# AT89S52.net
KiCad netlist of a schematic drawn in Altium Designer
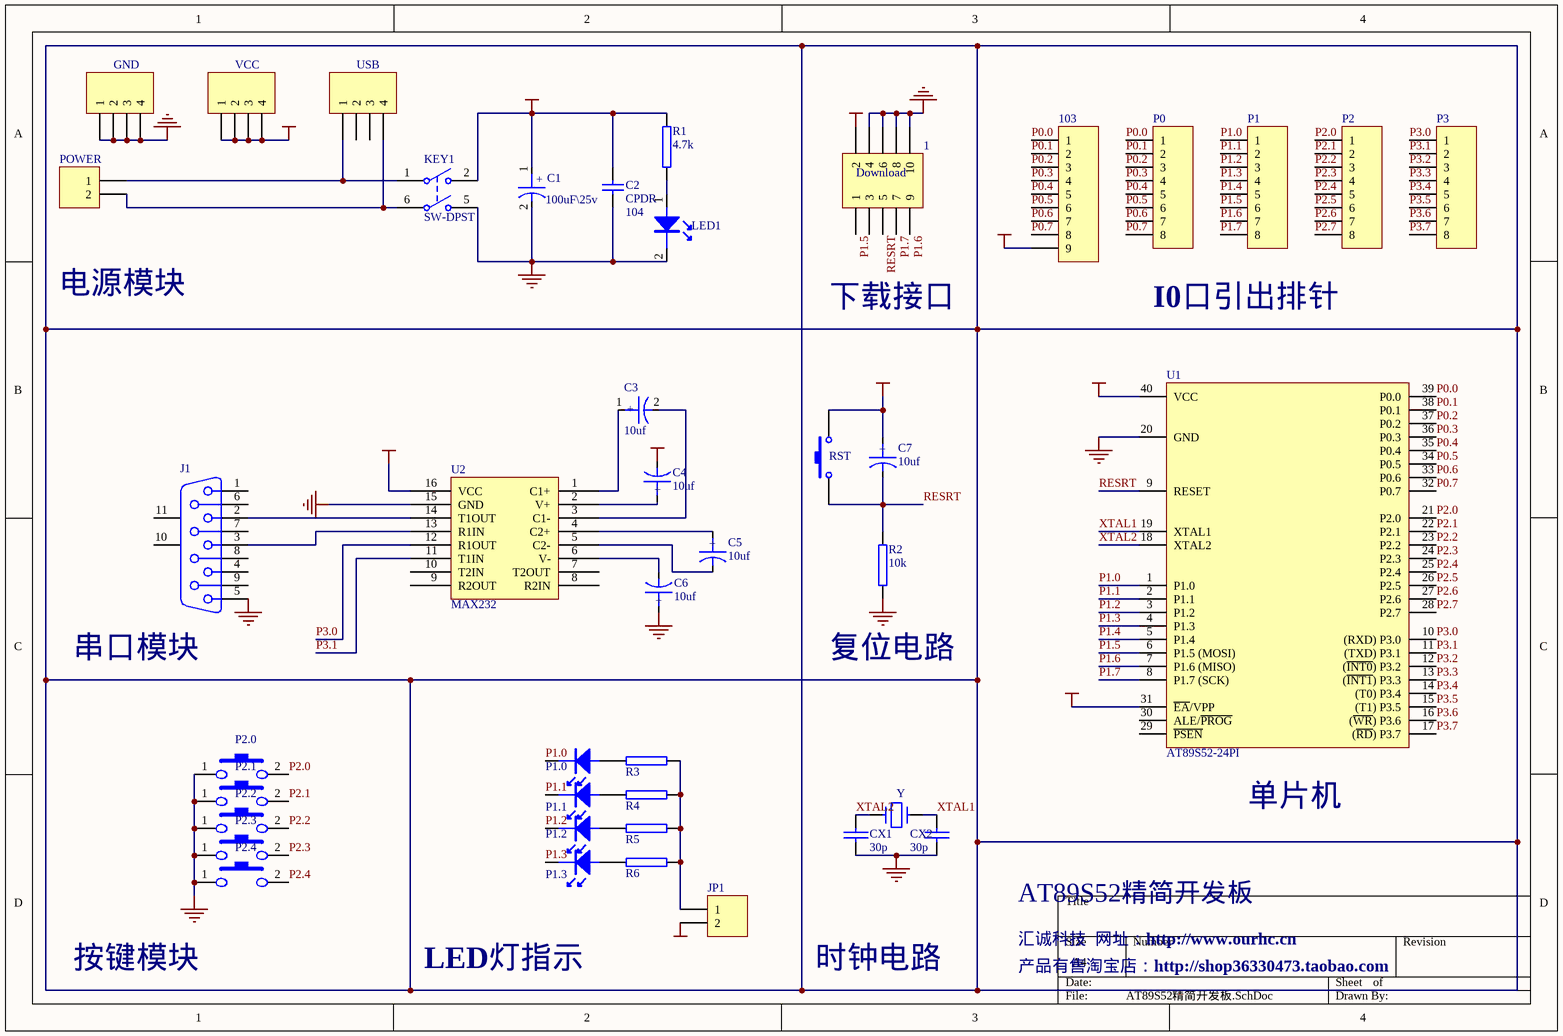
[diagram p0: AT89S52精简开发板.SchDoc]

(export (version "E")
  (design (tool "Eeschema 10.0.6"))
  (components
    (comp (ref "1")
      (value "Download")
      (footprint "HDR-2x5")
      (description "Header, 5-Pin, Dual row")
      (fields (field (name "PUBLISHER") "Altium Limited"))
      (libsource (lib "Miscellaneous Connectors") (part "Header 5X2"))
    )
    (comp (ref "103")
      (value "~")
      (footprint "HDR-9")
      (description "排针——9")
      (fields (field (name "PUBLISHER") "Altium Limited"))
      (libsource (lib "zxcourhc") (part "PZ_9"))
    )
    (comp (ref "C1")
      (value "100u~{F}25v")
      (footprint "C-DJ-6")
      (description "Capacitor")
      (libsource (lib "OldCow1 (1)") (part "CAPACITOR POL"))
    )
    (comp (ref "C2")
      (value "CPDR")
      (footprint "CPDR")
      (description "瓷片电容")
      (fields (field (name "ALTIUM_VALUE") "104") (field (name "PUBLISHER") "Altium Limited"))
      (libsource (lib "zxcourhc") (part "CPDR"))
    )
    (comp (ref "C3")
      (value "10uf")
      (footprint "C-DJ-4")
      (description "Capacitor")
      (libsource (lib "") (part "CAPACITOR POL_1"))
    )
    (comp (ref "C4")
      (value "10uf")
      (footprint "C-DJ-4")
      (description "Capacitor")
      (libsource (lib "*") (part "CAPACITOR POL"))
    )
    (comp (ref "C5")
      (value "10uf")
      (footprint "C-DJ-4")
      (description "Capacitor")
      (libsource (lib "*") (part "CAPACITOR POL"))
    )
    (comp (ref "C6")
      (value "10uf")
      (footprint "C-DJ-4")
      (description "Capacitor")
      (libsource (lib "*") (part "CAPACITOR POL"))
    )
    (comp (ref "C7")
      (value "10uf")
      (footprint "C-DJ-4")
      (description "Capacitor")
      (libsource (lib "*") (part "CAPACITOR POL"))
    )
    (comp (ref "CX1")
      (value "30p")
      (footprint "HDR1X2")
      (description "Capacitor")
      (libsource (lib "*") (part "CAP"))
    )
    (comp (ref "CX2")
      (value "30p")
      (footprint "HDR1X2")
      (description "Capacitor")
      (libsource (lib "*") (part "CAP"))
    )
    (comp (ref "GND")
      (value "~")
      (footprint "HDR1X4")
      (description "Header, 4-Pin")
      (fields (field (name "PUBLISHER") "Altium Limited"))
      (libsource (lib "Miscellaneous Connectors") (part "Header 4"))
    )
    (comp (ref "J1")
      (value "D Connector 9")
      (footprint "DSUB1.385-2H9")
      (description "Receptacle Assembly, 9 Position, Right Angle")
      (fields (field (name "PUBLISHER") "Altium Limited"))
      (libsource (lib "Miscellaneous Connectors") (part "D Connector 9"))
    )
    (comp (ref "JP1")
      (value "~")
      (footprint "HDR1X2")
      (description "Header, 2-Pin")
      (fields (field (name "PUBLISHER") "Altium Limited"))
      (libsource (lib "") (part "Header 2_1"))
    )
    (comp (ref "KEY1")
      (value "SW-DPST")
      (footprint "DPDT-6")
      (description "Double-Pole, Single-Throw Switch")
      (fields (field (name "PUBLISHER") "Altium Limited"))
      (libsource (lib "Miscellaneous Devices") (part "SW-DPST"))
    )
    (comp (ref "LED1") (value "LED") (footprint "LED") (libsource (lib "") (part "LED_1")))
    (comp (ref "P0")
      (value "~")
      (footprint "HDR-8")
      (description "排针——8")
      (fields (field (name "PUBLISHER") "Altium Limited"))
      (libsource (lib "zxcourhc") (part "PZ_8"))
    )
    (comp (ref "P1")
      (value "~")
      (footprint "HDR-8")
      (description "排针——8")
      (fields (field (name "PUBLISHER") "Altium Limited"))
      (libsource (lib "zxcourhc") (part "PZ_8"))
    )
    (comp (ref "P1.0") (value "LED") (footprint "HDR1X2") (libsource (lib "OldCow1 (1)") (part "LED")))
    (comp (ref "P1.1") (value "LED") (footprint "HDR1X2") (libsource (lib "OldCow1 (1)") (part "LED")))
    (comp (ref "P1.2") (value "LED") (footprint "HDR1X2") (libsource (lib "OldCow1 (1)") (part "LED")))
    (comp (ref "P1.3") (value "LED") (footprint "HDR1X2") (libsource (lib "OldCow1 (1)") (part "LED")))
    (comp (ref "P2")
      (value "~")
      (footprint "HDR-8")
      (description "排针——8")
      (fields (field (name "PUBLISHER") "Altium Limited"))
      (libsource (lib "zxcourhc") (part "PZ_8"))
    )
    (comp (ref "P2.0") (value "key1") (footprint "an-6*6") (libsource (lib "OldCow1 (1)") (part "key")))
    (comp (ref "P2.1") (value "key2") (footprint "an-6*6") (libsource (lib "OldCow1 (1)") (part "key")))
    (comp (ref "P2.2") (value "key3") (footprint "an-6*6") (libsource (lib "OldCow1 (1)") (part "key")))
    (comp (ref "P2.3") (value "key4") (footprint "an-6*6") (libsource (lib "OldCow1 (1)") (part "key")))
    (comp (ref "P2.4") (value "key4") (footprint "an-6*6") (libsource (lib "OldCow1 (1)") (part "key")))
    (comp (ref "P3")
      (value "~")
      (footprint "HDR-8")
      (description "排针——8")
      (fields (field (name "PUBLISHER") "Altium Limited"))
      (libsource (lib "zxcourhc") (part "PZ_8"))
    )
    (comp (ref "POWER")
      (value "~")
      (footprint "JK128")
      (description "Header, 2-Pin")
      (fields (field (name "PUBLISHER") "Altium Limited"))
      (libsource (lib "Miscellaneous Connectors") (part "Header 2"))
    )
    (comp (ref "R1") (value "4.7k") (footprint "RSE") (libsource (lib "*") (part "RES2")))
    (comp (ref "R2") (value "10k") (footprint "RSE") (libsource (lib "*") (part "RES2")))
    (comp (ref "R3") (value "470") (footprint "RSE") (libsource (lib "*") (part "RES2")))
    (comp (ref "R4") (value "470") (footprint "RSE") (libsource (lib "*") (part "RES2")))
    (comp (ref "R5") (value "470") (footprint "RSE") (libsource (lib "*") (part "RES2")))
    (comp (ref "R6") (value "470") (footprint "RSE") (libsource (lib "*") (part "RES2")))
    (comp (ref "RST")
      (value "~")
      (footprint "an-6*6")
      (description "Switch")
      (fields (field (name "PUBLISHER") "Altium Limited"))
      (libsource (lib "Miscellaneous Devices") (part "SW-PB"))
    )
    (comp (ref "U1")
      (value "AT89S52-24PI")
      (footprint "DIP-40")
      (description "8 位微处理器/40引脚")
      (fields (field (name "发布者") "磊元工作室"))
      (libsource (lib "MCU") (part "AT89S52-P"))
    )
    (comp (ref "U2") (value "MAX232") (footprint "DIP16") (libsource (lib "*") (part "MAX232")))
    (comp (ref "USB")
      (value "~")
      (footprint "USB-5V")
      (description "Header, 4-Pin")
      (fields (field (name "PUBLISHER") "Altium Limited"))
      (libsource (lib "Miscellaneous Connectors") (part "Header 4"))
    )
    (comp (ref "VCC")
      (value "~")
      (footprint "HDR1X4")
      (description "Header, 4-Pin")
      (fields (field (name "PUBLISHER") "Altium Limited"))
      (libsource (lib "Miscellaneous Connectors") (part "Header 4"))
    )
    (comp (ref "Y1")
      (value "Y")
      (footprint "JZ_ZC")
      (description "Crystal")
      (libsource (lib "*") (part "CRYSTAL"))
    )
  )
  (nets
    (net (code "1") (name "/P0.0") (class "Default")
      (node (ref "103") (pin "1") (pinfunction "1_1") (pintype "passive"))
      (node (ref "P0") (pin "1") (pinfunction "1_1") (pintype "passive"))
      (node (ref "U1") (pin "39") (pinfunction "P0.0_39") (pintype "passive"))
    )
    (net (code "2") (name "/P0.1") (class "Default")
      (node (ref "103") (pin "2") (pinfunction "2_2") (pintype "passive"))
      (node (ref "P0") (pin "2") (pinfunction "2_2") (pintype "passive"))
      (node (ref "U1") (pin "38") (pinfunction "P0.1_38") (pintype "passive"))
    )
    (net (code "3") (name "/P0.2") (class "Default")
      (node (ref "103") (pin "3") (pinfunction "3_3") (pintype "passive"))
      (node (ref "P0") (pin "3") (pinfunction "3_3") (pintype "passive"))
      (node (ref "U1") (pin "37") (pinfunction "P0.2_37") (pintype "passive"))
    )
    (net (code "4") (name "/P0.3") (class "Default")
      (node (ref "103") (pin "4") (pinfunction "4_4") (pintype "passive"))
      (node (ref "P0") (pin "4") (pinfunction "4_4") (pintype "passive"))
      (node (ref "U1") (pin "36") (pinfunction "P0.3_36") (pintype "passive"))
    )
    (net (code "5") (name "/P0.4") (class "Default")
      (node (ref "103") (pin "5") (pinfunction "5_5") (pintype "passive"))
      (node (ref "P0") (pin "5") (pinfunction "5_5") (pintype "passive"))
      (node (ref "U1") (pin "35") (pinfunction "P0.4_35") (pintype "passive"))
    )
    (net (code "6") (name "/P0.5") (class "Default")
      (node (ref "103") (pin "6") (pinfunction "6_6") (pintype "passive"))
      (node (ref "P0") (pin "6") (pinfunction "6_6") (pintype "passive"))
      (node (ref "U1") (pin "34") (pinfunction "P0.5_34") (pintype "passive"))
    )
    (net (code "7") (name "/P0.6") (class "Default")
      (node (ref "103") (pin "7") (pinfunction "7_7") (pintype "passive"))
      (node (ref "P0") (pin "7") (pinfunction "7_7") (pintype "passive"))
      (node (ref "U1") (pin "33") (pinfunction "P0.6_33") (pintype "passive"))
    )
    (net (code "8") (name "/P0.7") (class "Default")
      (node (ref "103") (pin "8") (pinfunction "8_8") (pintype "passive"))
      (node (ref "P0") (pin "8") (pinfunction "8_8") (pintype "passive"))
      (node (ref "U1") (pin "32") (pinfunction "P0.7_32") (pintype "passive"))
    )
    (net (code "9") (name "/P1.0") (class "Default")
      (node (ref "P1") (pin "1") (pinfunction "1_1") (pintype "passive"))
      (node (ref "P1.0") (pin "2") (pinfunction "K_2") (pintype "passive"))
      (node (ref "U1") (pin "1") (pinfunction "P1.0_1") (pintype "passive"))
    )
    (net (code "10") (name "/P1.1") (class "Default")
      (node (ref "P1") (pin "2") (pinfunction "2_2") (pintype "passive"))
      (node (ref "P1.1") (pin "2") (pinfunction "K_2") (pintype "passive"))
      (node (ref "U1") (pin "2") (pinfunction "P1.1_2") (pintype "passive"))
    )
    (net (code "11") (name "/P1.2") (class "Default")
      (node (ref "P1") (pin "3") (pinfunction "3_3") (pintype "passive"))
      (node (ref "P1.2") (pin "2") (pinfunction "K_2") (pintype "passive"))
      (node (ref "U1") (pin "3") (pinfunction "P1.2_3") (pintype "passive"))
    )
    (net (code "12") (name "/P1.3") (class "Default")
      (node (ref "P1") (pin "4") (pinfunction "4_4") (pintype "passive"))
      (node (ref "P1.3") (pin "2") (pinfunction "K_2") (pintype "passive"))
      (node (ref "U1") (pin "4") (pinfunction "P1.3_4") (pintype "passive"))
    )
    (net (code "13") (name "/P1.4") (class "Default")
      (node (ref "P1") (pin "5") (pinfunction "5_5") (pintype "passive"))
      (node (ref "U1") (pin "5") (pinfunction "P1.4_5") (pintype "passive"))
    )
    (net (code "14") (name "/P1.5") (class "Default")
      (node (ref "1") (pin "1") (pinfunction "1_1") (pintype "passive"))
      (node (ref "P1") (pin "6") (pinfunction "6_6") (pintype "passive"))
      (node (ref "U1") (pin "6") (pinfunction "P1.5_(MOSI)_6") (pintype "passive"))
    )
    (net (code "15") (name "/P1.6") (class "Default")
      (node (ref "1") (pin "9") (pinfunction "9_9") (pintype "passive"))
      (node (ref "P1") (pin "7") (pinfunction "7_7") (pintype "passive"))
      (node (ref "U1") (pin "7") (pinfunction "P1.6_(MISO)_7") (pintype "passive"))
    )
    (net (code "16") (name "/P1.7") (class "Default")
      (node (ref "1") (pin "7") (pinfunction "7_7") (pintype "passive"))
      (node (ref "P1") (pin "8") (pinfunction "8_8") (pintype "passive"))
      (node (ref "U1") (pin "8") (pinfunction "P1.7_(SCK)_8") (pintype "passive"))
    )
    (net (code "17") (name "/P2.0") (class "Default")
      (node (ref "P2") (pin "1") (pinfunction "1_1") (pintype "passive"))
      (node (ref "P2.0") (pin "2") (pinfunction "2_2") (pintype "passive"))
      (node (ref "U1") (pin "21") (pinfunction "P2.0_21") (pintype "passive"))
    )
    (net (code "18") (name "/P2.1") (class "Default")
      (node (ref "P2") (pin "2") (pinfunction "2_2") (pintype "passive"))
      (node (ref "P2.1") (pin "2") (pinfunction "2_2") (pintype "passive"))
      (node (ref "U1") (pin "22") (pinfunction "P2.1_22") (pintype "passive"))
    )
    (net (code "19") (name "/P2.2") (class "Default")
      (node (ref "P2") (pin "3") (pinfunction "3_3") (pintype "passive"))
      (node (ref "P2.2") (pin "2") (pinfunction "2_2") (pintype "passive"))
      (node (ref "U1") (pin "23") (pinfunction "P2.2_23") (pintype "passive"))
    )
    (net (code "20") (name "/P2.3") (class "Default")
      (node (ref "P2") (pin "4") (pinfunction "4_4") (pintype "passive"))
      (node (ref "P2.3") (pin "2") (pinfunction "2_2") (pintype "passive"))
      (node (ref "U1") (pin "24") (pinfunction "P2.3_24") (pintype "passive"))
    )
    (net (code "21") (name "/P2.4") (class "Default")
      (node (ref "P2") (pin "5") (pinfunction "5_5") (pintype "passive"))
      (node (ref "P2.4") (pin "2") (pinfunction "2_2") (pintype "passive"))
      (node (ref "U1") (pin "25") (pinfunction "P2.4_25") (pintype "passive"))
    )
    (net (code "22") (name "/P2.5") (class "Default")
      (node (ref "P2") (pin "6") (pinfunction "6_6") (pintype "passive"))
      (node (ref "U1") (pin "26") (pinfunction "P2.5_26") (pintype "passive"))
    )
    (net (code "23") (name "/P2.6") (class "Default")
      (node (ref "P2") (pin "7") (pinfunction "7_7") (pintype "passive"))
      (node (ref "U1") (pin "27") (pinfunction "P2.6_27") (pintype "passive"))
    )
    (net (code "24") (name "/P2.7") (class "Default")
      (node (ref "P2") (pin "8") (pinfunction "8_8") (pintype "passive"))
      (node (ref "U1") (pin "28") (pinfunction "P2.7_28") (pintype "passive"))
    )
    (net (code "25") (name "/P3.0") (class "Default")
      (node (ref "P3") (pin "1") (pinfunction "1_1") (pintype "passive"))
      (node (ref "U1") (pin "10") (pinfunction "(RXD)_P3.0_10") (pintype "passive"))
      (node (ref "U2") (pin "12") (pinfunction "R1OUT_12") (pintype "passive"))
    )
    (net (code "26") (name "/P3.1") (class "Default")
      (node (ref "P3") (pin "2") (pinfunction "2_2") (pintype "passive"))
      (node (ref "U1") (pin "11") (pinfunction "(TXD)_P3.1_11") (pintype "passive"))
      (node (ref "U2") (pin "11") (pinfunction "T1IN_11") (pintype "passive"))
    )
    (net (code "27") (name "/P3.2") (class "Default")
      (node (ref "P3") (pin "3") (pinfunction "3_3") (pintype "passive"))
      (node (ref "U1") (pin "12") (pinfunction "(~{INT0})_P3.2_12") (pintype "passive"))
    )
    (net (code "28") (name "/P3.3") (class "Default")
      (node (ref "P3") (pin "4") (pinfunction "4_4") (pintype "passive"))
      (node (ref "U1") (pin "13") (pinfunction "(~{INT1})_P3.3_13") (pintype "passive"))
    )
    (net (code "29") (name "/P3.4") (class "Default")
      (node (ref "P3") (pin "5") (pinfunction "5_5") (pintype "passive"))
      (node (ref "U1") (pin "14") (pinfunction "(T0)_P3.4_14") (pintype "passive"))
    )
    (net (code "30") (name "/P3.5") (class "Default")
      (node (ref "P3") (pin "6") (pinfunction "6_6") (pintype "passive"))
      (node (ref "U1") (pin "15") (pinfunction "(T1)_P3.5_15") (pintype "passive"))
    )
    (net (code "31") (name "/P3.6") (class "Default")
      (node (ref "P3") (pin "7") (pinfunction "7_7") (pintype "passive"))
      (node (ref "U1") (pin "16") (pinfunction "(~{WR})_P3.6_16") (pintype "passive"))
    )
    (net (code "32") (name "/P3.7") (class "Default")
      (node (ref "P3") (pin "8") (pinfunction "8_8") (pintype "passive"))
      (node (ref "U1") (pin "17") (pinfunction "(~{RD})_P3.7_17") (pintype "passive"))
    )
    (net (code "33") (name "/RESRT") (class "Default")
      (node (ref "1") (pin "5") (pinfunction "5_5") (pintype "passive"))
      (node (ref "C7") (pin "2") (pinfunction "2_2") (pintype "passive"))
      (node (ref "R2") (pin "2") (pinfunction "2_2") (pintype "passive"))
      (node (ref "RST") (pin "2") (pinfunction "2_2") (pintype "passive"))
      (node (ref "U1") (pin "9") (pinfunction "RESET_9") (pintype "passive"))
    )
    (net (code "34") (name "/XTAL1") (class "Default")
      (node (ref "CX2") (pin "1") (pinfunction "1_1") (pintype "passive"))
      (node (ref "U1") (pin "19") (pinfunction "XTAL1_19") (pintype "passive"))
      (node (ref "Y1") (pin "1") (pinfunction "1_1") (pintype "passive"))
    )
    (net (code "35") (name "/XTAL2") (class "Default")
      (node (ref "CX1") (pin "1") (pinfunction "1_1") (pintype "passive"))
      (node (ref "U1") (pin "18") (pinfunction "XTAL2_18") (pintype "passive"))
      (node (ref "Y1") (pin "2") (pinfunction "2_2") (pintype "passive"))
    )
    (net (code "36") (name "GND") (class "Default")
      (node (ref "1") (pin "10") (pinfunction "10_10") (pintype "passive"))
      (node (ref "1") (pin "4") (pinfunction "4_4") (pintype "passive"))
      (node (ref "1") (pin "6") (pinfunction "6_6") (pintype "passive"))
      (node (ref "1") (pin "8") (pinfunction "8_8") (pintype "passive"))
      (node (ref "C1") (pin "2") (pinfunction "2_2") (pintype "passive"))
      (node (ref "C2") (pin "1") (pinfunction "1_1") (pintype "passive"))
      (node (ref "C6") (pin "1") (pinfunction "1_1") (pintype "passive"))
      (node (ref "CX1") (pin "2") (pinfunction "2_2") (pintype "passive"))
      (node (ref "CX2") (pin "2") (pinfunction "2_2") (pintype "passive"))
      (node (ref "GND") (pin "1") (pinfunction "1_1") (pintype "passive"))
      (node (ref "GND") (pin "2") (pinfunction "2_2") (pintype "passive"))
      (node (ref "GND") (pin "3") (pinfunction "3_3") (pintype "passive"))
      (node (ref "GND") (pin "4") (pinfunction "4_4") (pintype "passive"))
      (node (ref "J1") (pin "5") (pinfunction "5_5") (pintype "passive"))
      (node (ref "KEY1") (pin "5") (pinfunction "NO2_5") (pintype "passive"))
      (node (ref "LED1") (pin "2") (pinfunction "K_2") (pintype "passive"))
      (node (ref "P2.0") (pin "1") (pinfunction "1_1") (pintype "passive"))
      (node (ref "P2.1") (pin "1") (pinfunction "1_1") (pintype "passive"))
      (node (ref "P2.2") (pin "1") (pinfunction "1_1") (pintype "passive"))
      (node (ref "P2.3") (pin "1") (pinfunction "1_1") (pintype "passive"))
      (node (ref "P2.4") (pin "1") (pinfunction "1_1") (pintype "passive"))
      (node (ref "R2") (pin "1") (pinfunction "1_1") (pintype "passive"))
      (node (ref "U1") (pin "20") (pinfunction "GND_20") (pintype "power_in"))
      (node (ref "U2") (pin "15") (pinfunction "GND_15") (pintype "passive"))
    )
    (net (code "37") (name "Net-(JP1-Pad1)") (class "Default")
      (node (ref "JP1") (pin "1") (pinfunction "1_1") (pintype "passive"))
      (node (ref "R3") (pin "1") (pinfunction "1_1") (pintype "passive"))
      (node (ref "R4") (pin "1") (pinfunction "1_1") (pintype "passive"))
      (node (ref "R5") (pin "1") (pinfunction "1_1") (pintype "passive"))
      (node (ref "R6") (pin "1") (pinfunction "1_1") (pintype "passive"))
    )
    (net (code "38") (name "Net-(KEY1-COMMON1)") (class "Default")
      (node (ref "KEY1") (pin "1") (pinfunction "COMMON1_1") (pintype "passive"))
      (node (ref "POWER") (pin "1") (pinfunction "1_1") (pintype "passive"))
      (node (ref "USB") (pin "1") (pinfunction "1_1") (pintype "passive"))
    )
    (net (code "39") (name "Net-(KEY1-COMMON2)") (class "Default")
      (node (ref "KEY1") (pin "6") (pinfunction "COMMON2_6") (pintype "passive"))
      (node (ref "POWER") (pin "2") (pinfunction "2_2") (pintype "passive"))
      (node (ref "USB") (pin "4") (pinfunction "4_4") (pintype "passive"))
    )
    (net (code "40") (name "Net-(LED1-A)") (class "Default")
      (node (ref "LED1") (pin "1") (pinfunction "A_1") (pintype "passive"))
      (node (ref "R1") (pin "2") (pinfunction "2_2") (pintype "passive"))
    )
    (net (code "41") (name "Net-(P1.0-A)") (class "Default")
      (node (ref "P1.0") (pin "1") (pinfunction "A_1") (pintype "passive"))
      (node (ref "R3") (pin "2") (pinfunction "2_2") (pintype "passive"))
    )
    (net (code "42") (name "Net-(P1.1-A)") (class "Default")
      (node (ref "P1.1") (pin "1") (pinfunction "A_1") (pintype "passive"))
      (node (ref "R4") (pin "2") (pinfunction "2_2") (pintype "passive"))
    )
    (net (code "43") (name "Net-(P1.2-A)") (class "Default")
      (node (ref "P1.2") (pin "1") (pinfunction "A_1") (pintype "passive"))
      (node (ref "R5") (pin "2") (pinfunction "2_2") (pintype "passive"))
    )
    (net (code "44") (name "Net-(P1.3-A)") (class "Default")
      (node (ref "P1.3") (pin "1") (pinfunction "A_1") (pintype "passive"))
      (node (ref "R6") (pin "2") (pinfunction "2_2") (pintype "passive"))
    )
    (net (code "45") (name "Net-(U2-C1+)") (class "Default")
      (node (ref "C3") (pin "1") (pinfunction "1_1") (pintype "passive"))
      (node (ref "U2") (pin "1") (pinfunction "C1+_1") (pintype "passive"))
    )
    (net (code "46") (name "Net-(U2-C1-)") (class "Default")
      (node (ref "C3") (pin "2") (pinfunction "2_2") (pintype "passive"))
      (node (ref "U2") (pin "3") (pinfunction "C1-_3") (pintype "passive"))
    )
    (net (code "47") (name "Net-(U2-C2+)") (class "Default")
      (node (ref "C5") (pin "1") (pinfunction "1_1") (pintype "passive"))
      (node (ref "U2") (pin "4") (pinfunction "C2+_4") (pintype "passive"))
    )
    (net (code "48") (name "Net-(U2-C2-)") (class "Default")
      (node (ref "C5") (pin "2") (pinfunction "2_2") (pintype "passive"))
      (node (ref "U2") (pin "5") (pinfunction "C2-_5") (pintype "passive"))
    )
    (net (code "49") (name "Net-(U2-R1IN)") (class "Default")
      (node (ref "J1") (pin "3") (pinfunction "3_3") (pintype "passive"))
      (node (ref "U2") (pin "13") (pinfunction "R1IN_13") (pintype "passive"))
    )
    (net (code "50") (name "Net-(U2-T1OUT)") (class "Default")
      (node (ref "J1") (pin "2") (pinfunction "2_2") (pintype "passive"))
      (node (ref "U2") (pin "14") (pinfunction "T1OUT_14") (pintype "passive"))
    )
    (net (code "51") (name "Net-(U2-V+)") (class "Default")
      (node (ref "C4") (pin "1") (pinfunction "1_1") (pintype "passive"))
      (node (ref "U2") (pin "2") (pinfunction "V+_2") (pintype "passive"))
    )
    (net (code "52") (name "Net-(U2-V-)") (class "Default")
      (node (ref "C6") (pin "2") (pinfunction "2_2") (pintype "passive"))
      (node (ref "U2") (pin "6") (pinfunction "V-_6") (pintype "passive"))
    )
    (net (code "53") (name "VCC") (class "Default")
      (node (ref "1") (pin "2") (pinfunction "2_2") (pintype "passive"))
      (node (ref "103") (pin "9") (pinfunction "9_9") (pintype "passive"))
      (node (ref "C1") (pin "1") (pinfunction "1_1") (pintype "passive"))
      (node (ref "C2") (pin "2") (pinfunction "2_2") (pintype "passive"))
      (node (ref "C4") (pin "2") (pinfunction "2_2") (pintype "passive"))
      (node (ref "C7") (pin "1") (pinfunction "1_1") (pintype "passive"))
      (node (ref "JP1") (pin "2") (pinfunction "2_2") (pintype "passive"))
      (node (ref "KEY1") (pin "2") (pinfunction "NO1_2") (pintype "passive"))
      (node (ref "R1") (pin "1") (pinfunction "1_1") (pintype "passive"))
      (node (ref "RST") (pin "1") (pinfunction "1_1") (pintype "passive"))
      (node (ref "U1") (pin "31") (pinfunction "~{EA}/VPP_31") (pintype "passive"))
      (node (ref "U1") (pin "40") (pinfunction "VCC_40") (pintype "power_in"))
      (node (ref "U2") (pin "16") (pinfunction "VCC_16") (pintype "passive"))
      (node (ref "VCC") (pin "1") (pinfunction "1_1") (pintype "passive"))
      (node (ref "VCC") (pin "2") (pinfunction "2_2") (pintype "passive"))
      (node (ref "VCC") (pin "3") (pinfunction "3_3") (pintype "passive"))
      (node (ref "VCC") (pin "4") (pinfunction "4_4") (pintype "passive"))
    )
    (net (code "54") (name "unconnected-(1-Pad3)") (class "Default")
      (node (ref "1") (pin "3") (pinfunction "3_3") (pintype "passive"))
    )
    (net (code "55") (name "unconnected-(J1-MH1-Pad10)") (class "Default")
      (node (ref "J1") (pin "10") (pinfunction "MH1_10") (pintype "passive"))
    )
    (net (code "56") (name "unconnected-(J1-MH2-Pad11)") (class "Default")
      (node (ref "J1") (pin "11") (pinfunction "MH2_11") (pintype "passive"))
    )
    (net (code "57") (name "unconnected-(J1-Pad1)") (class "Default")
      (node (ref "J1") (pin "1") (pinfunction "1_1") (pintype "passive"))
    )
    (net (code "58") (name "unconnected-(J1-Pad4)") (class "Default")
      (node (ref "J1") (pin "4") (pinfunction "4_4") (pintype "passive"))
    )
    (net (code "59") (name "unconnected-(J1-Pad6)") (class "Default")
      (node (ref "J1") (pin "6") (pinfunction "6_6") (pintype "passive"))
    )
    (net (code "60") (name "unconnected-(J1-Pad7)") (class "Default")
      (node (ref "J1") (pin "7") (pinfunction "7_7") (pintype "passive"))
    )
    (net (code "61") (name "unconnected-(J1-Pad8)") (class "Default")
      (node (ref "J1") (pin "8") (pinfunction "8_8") (pintype "passive"))
    )
    (net (code "62") (name "unconnected-(J1-Pad9)") (class "Default")
      (node (ref "J1") (pin "9") (pinfunction "9_9") (pintype "passive"))
    )
    (net (code "63") (name "unconnected-(U1-ALE{slash}~{PROG}-Pad30)") (class "Default")
      (node (ref "U1") (pin "30") (pinfunction "ALE/~{PROG}_30") (pintype "passive"))
    )
    (net (code "64") (name "unconnected-(U1-~{PSEN}-Pad29)") (class "Default")
      (node (ref "U1") (pin "29") (pinfunction "~{PSEN}_29") (pintype "passive"))
    )
    (net (code "65") (name "unconnected-(U2-R2IN-Pad8)") (class "Default")
      (node (ref "U2") (pin "8") (pinfunction "R2IN_8") (pintype "passive"))
    )
    (net (code "66") (name "unconnected-(U2-R2OUT-Pad9)") (class "Default")
      (node (ref "U2") (pin "9") (pinfunction "R2OUT_9") (pintype "passive"))
    )
    (net (code "67") (name "unconnected-(U2-T2IN-Pad10)") (class "Default")
      (node (ref "U2") (pin "10") (pinfunction "T2IN_10") (pintype "passive"))
    )
    (net (code "68") (name "unconnected-(U2-T2OUT-Pad7)") (class "Default")
      (node (ref "U2") (pin "7") (pinfunction "T2OUT_7") (pintype "passive"))
    )
    (net (code "69") (name "unconnected-(USB-Pad2)") (class "Default")
      (node (ref "USB") (pin "2") (pinfunction "2_2") (pintype "passive"))
    )
    (net (code "70") (name "unconnected-(USB-Pad3)") (class "Default")
      (node (ref "USB") (pin "3") (pinfunction "3_3") (pintype "passive"))
    )
  )
)
